# DE-260124.net
KiCad netlist of a schematic drawn in Altium Designer
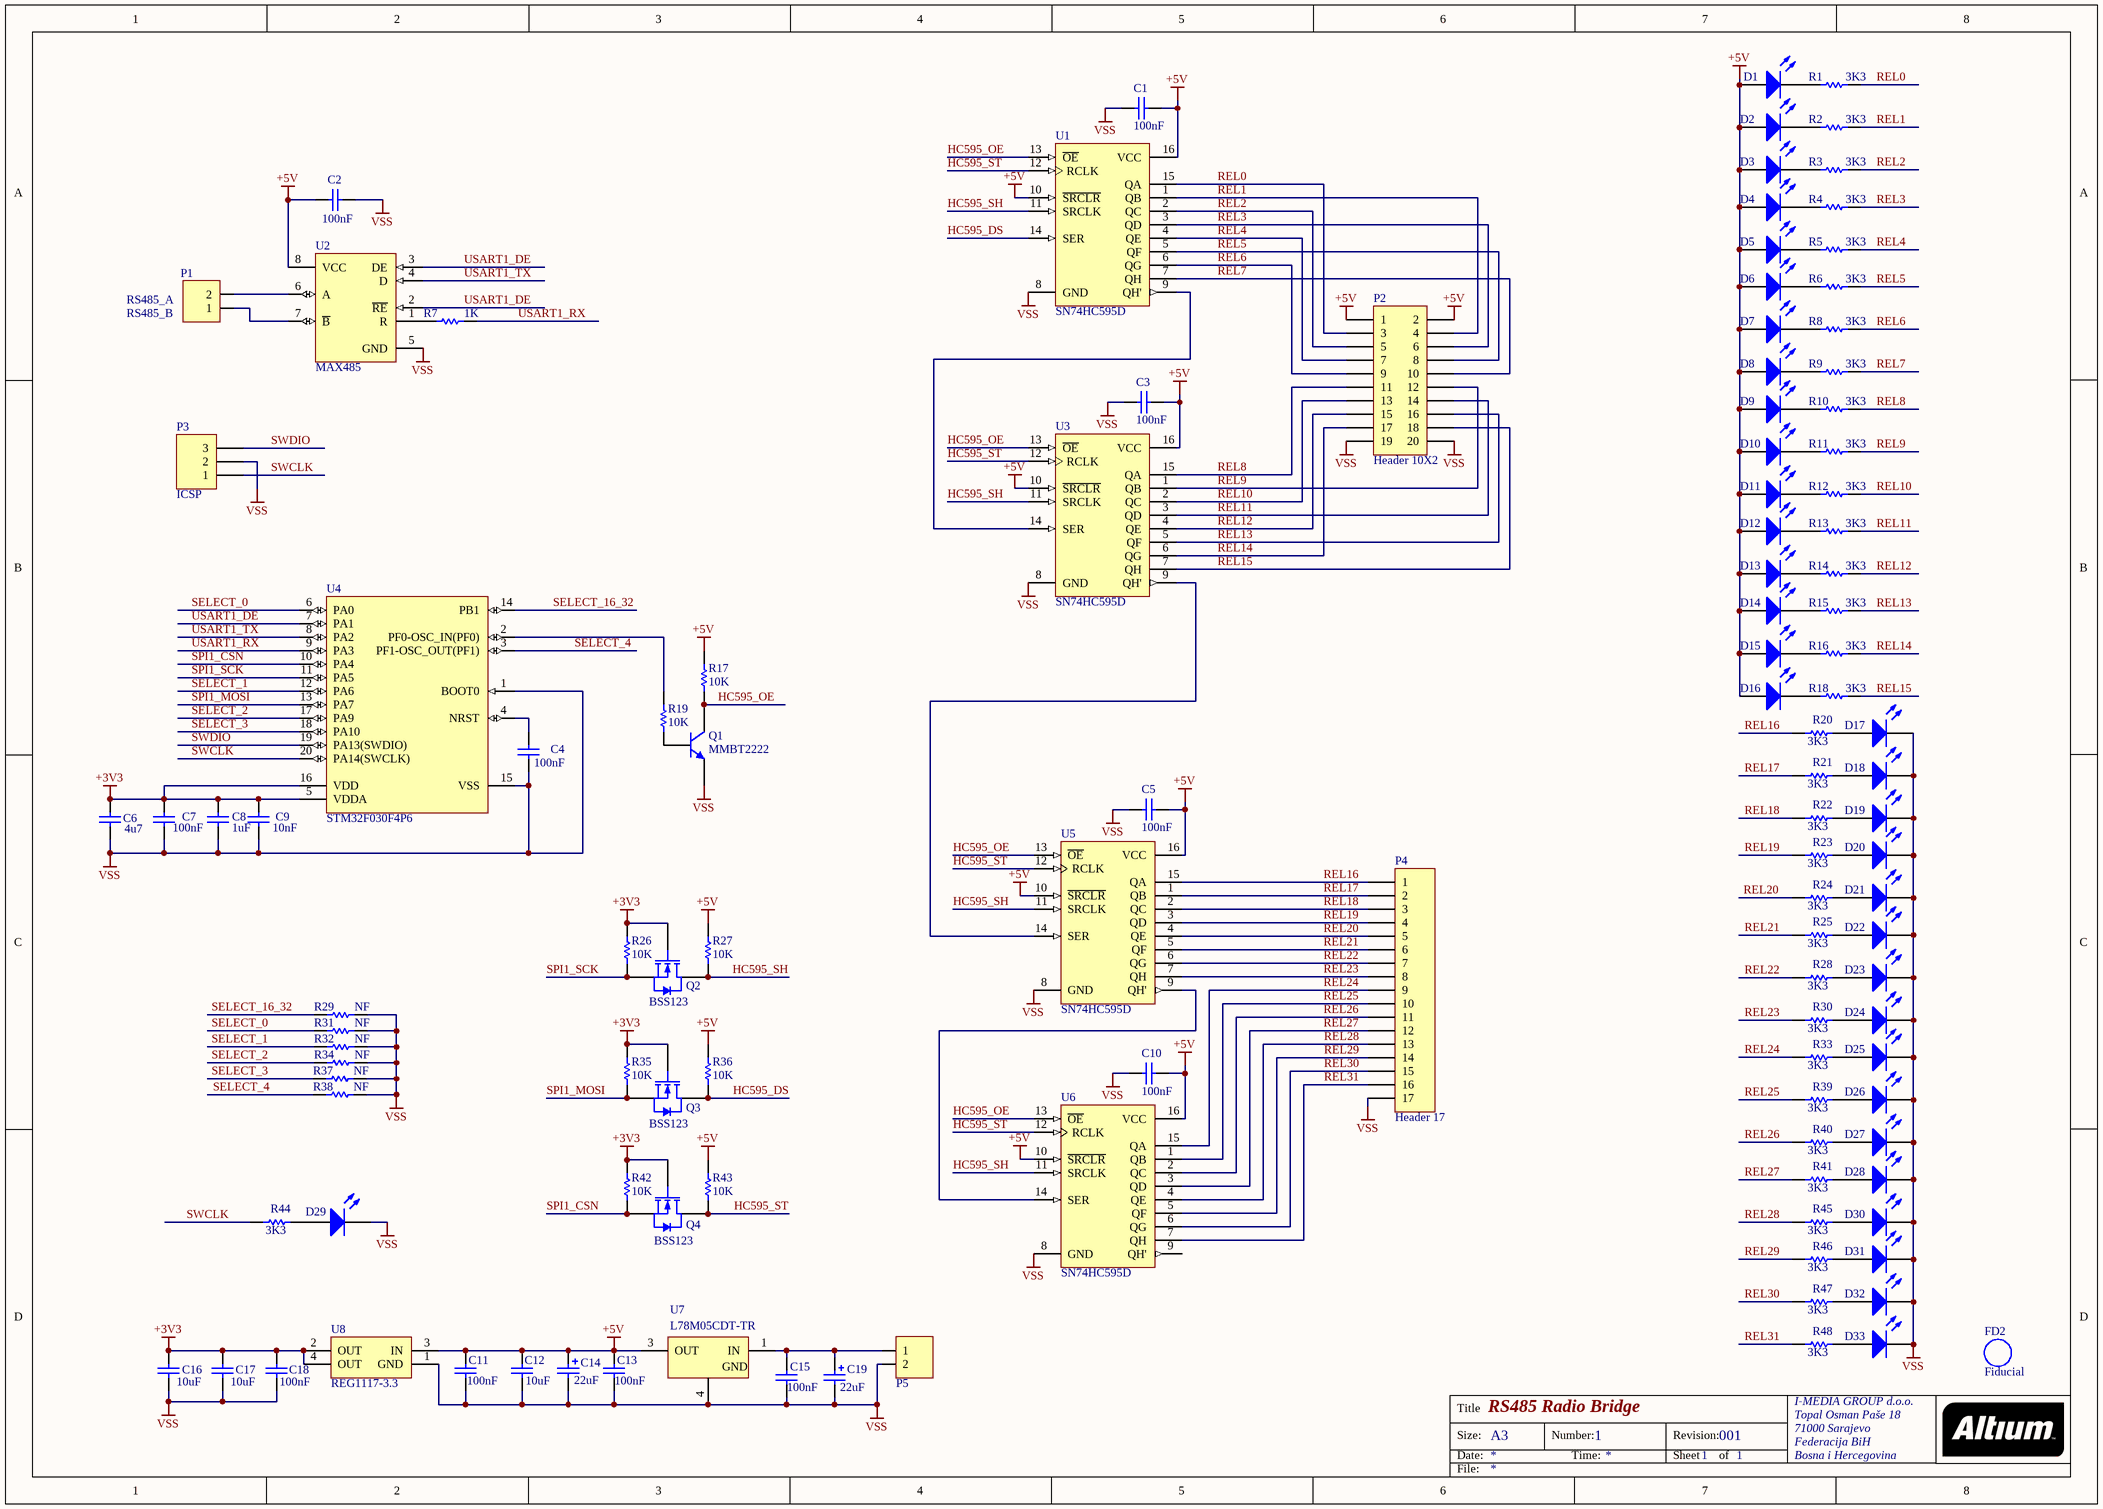
[diagram p0: DE-260124.SchDoc]

(export (version "E")
  (design (tool "Eeschema 10.0.6"))
  (components
    (comp (ref "C1")
      (value "100nF")
      (footprint "0603")
      (description "Ceramic Chip Capacitor - Standard")
      (libsource (lib "DE-251215") (part "C0603"))
    )
    (comp (ref "C2")
      (value "100nF")
      (footprint "0603")
      (description "Ceramic Chip Capacitor - Standard")
      (libsource (lib "KEMET Chip Capacitor") (part "C0603"))
    )
    (comp (ref "C3")
      (value "100nF")
      (footprint "0603")
      (description "Ceramic Chip Capacitor - Standard")
      (libsource (lib "DE-251215") (part "C0603"))
    )
    (comp (ref "C4")
      (value "100nF")
      (footprint "0603")
      (description "Ceramic Chip Capacitor - Standard")
      (libsource (lib "KEMET Chip Capacitor") (part "C0603"))
    )
    (comp (ref "C5")
      (value "100nF")
      (footprint "0603")
      (description "Ceramic Chip Capacitor - Standard")
      (libsource (lib "DE-251215") (part "C0603"))
    )
    (comp (ref "C6")
      (value "4u7")
      (footprint "0805")
      (description "Ceramic Chip Capacitor - Standard")
      (libsource (lib "KEMET Chip Capacitor") (part "C0805"))
    )
    (comp (ref "C7")
      (value "100nF")
      (footprint "0603")
      (description "Ceramic Chip Capacitor - Standard")
      (libsource (lib "KEMET Chip Capacitor") (part "C0603"))
    )
    (comp (ref "C8")
      (value "1uF")
      (footprint "0603")
      (description "Ceramic Chip Capacitor - Standard")
      (libsource (lib "KEMET Chip Capacitor") (part "C0603"))
    )
    (comp (ref "C9")
      (value "10nF")
      (footprint "0603")
      (description "Ceramic Chip Capacitor - Standard")
      (libsource (lib "KEMET Chip Capacitor") (part "C0603"))
    )
    (comp (ref "C10")
      (value "100nF")
      (footprint "0603")
      (description "Ceramic Chip Capacitor - Standard")
      (libsource (lib "DE-251215") (part "C0603"))
    )
    (comp (ref "C11")
      (value "100nF")
      (footprint "0603")
      (description "Ceramic Chip Capacitor - Standard")
      (libsource (lib "DE-251215") (part "C0603"))
    )
    (comp (ref "C12")
      (value "10uF")
      (footprint "0805")
      (description "Ceramic Chip Capacitor - Standard")
      (libsource (lib "DE-200216_03") (part "C0805"))
    )
    (comp (ref "C13")
      (value "100nF")
      (footprint "0603")
      (description "Ceramic Chip Capacitor - Standard")
      (libsource (lib "DE-251215") (part "C0603"))
    )
    (comp (ref "C14")
      (value "22uF")
      (footprint "CAPPR2-5X11")
      (description "Aluminum Electrolytic Capacitor, Radial Style with Long Leads: 47uF, 35V")
      (libsource (lib "DE-260124") (part "EKA00AA247F00"))
    )
    (comp (ref "C15")
      (value "100nF")
      (footprint "0603")
      (description "Ceramic Chip Capacitor - Standard")
      (libsource (lib "DE-251215") (part "C0603"))
    )
    (comp (ref "C16")
      (value "10uF")
      (footprint "0805")
      (description "Ceramic Chip Capacitor - Standard")
      (libsource (lib "DE-251215") (part "C0805"))
    )
    (comp (ref "C17")
      (value "10uF")
      (footprint "0805")
      (description "Ceramic Chip Capacitor - Standard")
      (libsource (lib "DE-251215") (part "C0805"))
    )
    (comp (ref "C18")
      (value "100nF")
      (footprint "0603")
      (description "Ceramic Chip Capacitor - Standard")
      (libsource (lib "DE-251215") (part "C0603"))
    )
    (comp (ref "C19")
      (value "22uF")
      (footprint "CAPPR2-5X11")
      (description "Aluminum Electrolytic Capacitor, Radial Style with Long Leads: 47uF, 35V")
      (libsource (lib "DE-260124") (part "EKA00AA247F00"))
    )
    (comp (ref "D1")
      (value "LED_RED")
      (footprint "1.6X0.8X0.8")
      (description "High Performance Chip LED, Red")
      (libsource (lib "DE-260124") (part "HSMZ-C190"))
    )
    (comp (ref "D2")
      (value "LED_RED")
      (footprint "1.6X0.8X0.8")
      (description "High Performance Chip LED, Red")
      (libsource (lib "DE-260124") (part "HSMZ-C190"))
    )
    (comp (ref "D3")
      (value "LED_RED")
      (footprint "1.6X0.8X0.8")
      (description "High Performance Chip LED, Red")
      (libsource (lib "DE-260124") (part "HSMZ-C190"))
    )
    (comp (ref "D4")
      (value "LED_RED")
      (footprint "1.6X0.8X0.8")
      (description "High Performance Chip LED, Red")
      (libsource (lib "DE-260124") (part "HSMZ-C190"))
    )
    (comp (ref "D5")
      (value "LED_RED")
      (footprint "1.6X0.8X0.8")
      (description "High Performance Chip LED, Red")
      (libsource (lib "DE-260124") (part "HSMZ-C190"))
    )
    (comp (ref "D6")
      (value "LED_RED")
      (footprint "1.6X0.8X0.8")
      (description "High Performance Chip LED, Red")
      (libsource (lib "DE-260124") (part "HSMZ-C190"))
    )
    (comp (ref "D7")
      (value "LED_RED")
      (footprint "1.6X0.8X0.8")
      (description "High Performance Chip LED, Red")
      (libsource (lib "DE-260124") (part "HSMZ-C190"))
    )
    (comp (ref "D8")
      (value "LED_RED")
      (footprint "1.6X0.8X0.8")
      (description "High Performance Chip LED, Red")
      (libsource (lib "DE-260124") (part "HSMZ-C190"))
    )
    (comp (ref "D9")
      (value "LED_RED")
      (footprint "1.6X0.8X0.8")
      (description "High Performance Chip LED, Red")
      (libsource (lib "DE-260124") (part "HSMZ-C190"))
    )
    (comp (ref "D10")
      (value "LED_RED")
      (footprint "1.6X0.8X0.8")
      (description "High Performance Chip LED, Red")
      (libsource (lib "DE-260124") (part "HSMZ-C190"))
    )
    (comp (ref "D11")
      (value "LED_RED")
      (footprint "1.6X0.8X0.8")
      (description "High Performance Chip LED, Red")
      (libsource (lib "DE-260124") (part "HSMZ-C190"))
    )
    (comp (ref "D12")
      (value "LED_RED")
      (footprint "1.6X0.8X0.8")
      (description "High Performance Chip LED, Red")
      (libsource (lib "DE-260124") (part "HSMZ-C190"))
    )
    (comp (ref "D13")
      (value "LED_RED")
      (footprint "1.6X0.8X0.8")
      (description "High Performance Chip LED, Red")
      (libsource (lib "DE-260124") (part "HSMZ-C190"))
    )
    (comp (ref "D14")
      (value "LED_RED")
      (footprint "1.6X0.8X0.8")
      (description "High Performance Chip LED, Red")
      (libsource (lib "DE-260124") (part "HSMZ-C190"))
    )
    (comp (ref "D15")
      (value "LED_RED")
      (footprint "1.6X0.8X0.8")
      (description "High Performance Chip LED, Red")
      (libsource (lib "DE-260124") (part "HSMZ-C190"))
    )
    (comp (ref "D16")
      (value "LED_RED")
      (footprint "1.6X0.8X0.8")
      (description "High Performance Chip LED, Red")
      (libsource (lib "DE-260124") (part "HSMZ-C190"))
    )
    (comp (ref "D17")
      (value "LED_RED")
      (footprint "1.6X0.8X0.8")
      (description "High Performance Chip LED, Red")
      (libsource (lib "DE-260124") (part "HSMZ-C190"))
    )
    (comp (ref "D18")
      (value "LED_RED")
      (footprint "1.6X0.8X0.8")
      (description "High Performance Chip LED, Red")
      (libsource (lib "DE-260124") (part "HSMZ-C190"))
    )
    (comp (ref "D19")
      (value "LED_RED")
      (footprint "1.6X0.8X0.8")
      (description "High Performance Chip LED, Red")
      (libsource (lib "DE-260124") (part "HSMZ-C190"))
    )
    (comp (ref "D20")
      (value "LED_RED")
      (footprint "1.6X0.8X0.8")
      (description "High Performance Chip LED, Red")
      (libsource (lib "DE-260124") (part "HSMZ-C190"))
    )
    (comp (ref "D21")
      (value "LED_RED")
      (footprint "1.6X0.8X0.8")
      (description "High Performance Chip LED, Red")
      (libsource (lib "DE-260124") (part "HSMZ-C190"))
    )
    (comp (ref "D22")
      (value "LED_RED")
      (footprint "1.6X0.8X0.8")
      (description "High Performance Chip LED, Red")
      (libsource (lib "DE-260124") (part "HSMZ-C190"))
    )
    (comp (ref "D23")
      (value "LED_RED")
      (footprint "1.6X0.8X0.8")
      (description "High Performance Chip LED, Red")
      (libsource (lib "DE-260124") (part "HSMZ-C190"))
    )
    (comp (ref "D24")
      (value "LED_RED")
      (footprint "1.6X0.8X0.8")
      (description "High Performance Chip LED, Red")
      (libsource (lib "DE-260124") (part "HSMZ-C190"))
    )
    (comp (ref "D25")
      (value "LED_RED")
      (footprint "1.6X0.8X0.8")
      (description "High Performance Chip LED, Red")
      (libsource (lib "DE-260124") (part "HSMZ-C190"))
    )
    (comp (ref "D26")
      (value "LED_RED")
      (footprint "1.6X0.8X0.8")
      (description "High Performance Chip LED, Red")
      (libsource (lib "DE-260124") (part "HSMZ-C190"))
    )
    (comp (ref "D27")
      (value "LED_RED")
      (footprint "1.6X0.8X0.8")
      (description "High Performance Chip LED, Red")
      (libsource (lib "DE-260124") (part "HSMZ-C190"))
    )
    (comp (ref "D28")
      (value "LED_RED")
      (footprint "1.6X0.8X0.8")
      (description "High Performance Chip LED, Red")
      (libsource (lib "DE-260124") (part "HSMZ-C190"))
    )
    (comp (ref "D29")
      (value "LED_RED")
      (footprint "1.6X0.8X0.8")
      (description "High Performance Chip LED, Red")
      (libsource (lib "DE-260124") (part "HSMZ-C190"))
    )
    (comp (ref "D30")
      (value "LED_RED")
      (footprint "1.6X0.8X0.8")
      (description "High Performance Chip LED, Red")
      (libsource (lib "DE-260124") (part "HSMZ-C190"))
    )
    (comp (ref "D31")
      (value "LED_RED")
      (footprint "1.6X0.8X0.8")
      (description "High Performance Chip LED, Red")
      (libsource (lib "DE-260124") (part "HSMZ-C190"))
    )
    (comp (ref "D32")
      (value "LED_RED")
      (footprint "1.6X0.8X0.8")
      (description "High Performance Chip LED, Red")
      (libsource (lib "DE-260124") (part "HSMZ-C190"))
    )
    (comp (ref "D33")
      (value "LED_RED")
      (footprint "1.6X0.8X0.8")
      (description "High Performance Chip LED, Red")
      (libsource (lib "DE-260124") (part "HSMZ-C190"))
    )
    (comp (ref "FD2")
      (value "Fiducial")
      (footprint "Fiducial")
      (description "Fiduchial mark")
      (libsource (lib "DE-260124") (part "Fiduchial"))
    )
    (comp (ref "P1")
      (value "TERMINAL BLOK 2")
      (footprint "TERMINAL BLOK 2")
      (description "2 pinski terminal blok")
      (libsource (lib "DE-280817") (part "TERMINAL BLOK 2"))
    )
    (comp (ref "P2")
      (value "Header 10X2")
      (footprint "HDR2X10")
      (description "Header, 10-Pin, Dual row")
      (libsource (lib "Miscellaneous Connectors") (part "Header 10X2"))
    )
    (comp (ref "P3")
      (value "ICSP")
      (footprint "HDR1X3")
      (description "Header, 3-Pin")
      (libsource (lib "Miscellaneous Connectors") (part "Header 3"))
    )
    (comp (ref "P4")
      (value "Header 17")
      (footprint "HDR1X17")
      (description "Header, 17-Pin")
      (libsource (lib "Miscellaneous Connectors") (part "Header 17"))
    )
    (comp (ref "P5")
      (value "TERMINAL BLOK 2")
      (footprint "TERMINAL BLOK 2")
      (description "2 pinski terminal blok")
      (libsource (lib "DE-260124") (part "TERMINAL BLOK 2"))
    )
    (comp (ref "Q1")
      (value "MMBT2222")
      (footprint "SOT23_N")
      (description "NPN General-purpose Transistor")
      (libsource (lib "DE-260124") (part "BC817"))
    )
    (comp (ref "Q2")
      (value "BSS123")
      (footprint "SOT23_N")
      (description "N-channel Enhancement Mode Vertical D-MOSFET")
      (libsource (lib "DE-260124") (part "BSS123"))
    )
    (comp (ref "Q3")
      (value "BSS123")
      (footprint "SOT23_N")
      (description "N-channel Enhancement Mode Vertical D-MOSFET")
      (libsource (lib "DE-260124") (part "BSS123"))
    )
    (comp (ref "Q4")
      (value "BSS123")
      (footprint "SOT23_N")
      (description "N-channel Enhancement Mode Vertical D-MOSFET")
      (libsource (lib "DE-260124") (part "BSS123"))
    )
    (comp (ref "R1")
      (value "3K3")
      (footprint "ERA-0603")
      (libsource (lib "Panasonic Resistor") (part "ERA3Y"))
    )
    (comp (ref "R2")
      (value "3K3")
      (footprint "ERA-0603")
      (libsource (lib "Panasonic Resistor") (part "ERA3Y"))
    )
    (comp (ref "R3")
      (value "3K3")
      (footprint "ERA-0603")
      (libsource (lib "Panasonic Resistor") (part "ERA3Y"))
    )
    (comp (ref "R4")
      (value "3K3")
      (footprint "ERA-0603")
      (libsource (lib "Panasonic Resistor") (part "ERA3Y"))
    )
    (comp (ref "R5")
      (value "3K3")
      (footprint "ERA-0603")
      (libsource (lib "Panasonic Resistor") (part "ERA3Y"))
    )
    (comp (ref "R6")
      (value "3K3")
      (footprint "ERA-0603")
      (libsource (lib "Panasonic Resistor") (part "ERA3Y"))
    )
    (comp (ref "R7") (value "1K") (footprint "ERA-0603") (libsource (lib "DE-280817") (part "ERA6Y")))
    (comp (ref "R8")
      (value "3K3")
      (footprint "ERA-0603")
      (libsource (lib "Panasonic Resistor") (part "ERA3Y"))
    )
    (comp (ref "R9")
      (value "3K3")
      (footprint "ERA-0603")
      (libsource (lib "Panasonic Resistor") (part "ERA3Y"))
    )
    (comp (ref "R10")
      (value "3K3")
      (footprint "ERA-0603")
      (libsource (lib "Panasonic Resistor") (part "ERA3Y"))
    )
    (comp (ref "R11")
      (value "3K3")
      (footprint "ERA-0603")
      (libsource (lib "Panasonic Resistor") (part "ERA3Y"))
    )
    (comp (ref "R12")
      (value "3K3")
      (footprint "ERA-0603")
      (libsource (lib "Panasonic Resistor") (part "ERA3Y"))
    )
    (comp (ref "R13")
      (value "3K3")
      (footprint "ERA-0603")
      (libsource (lib "Panasonic Resistor") (part "ERA3Y"))
    )
    (comp (ref "R14")
      (value "3K3")
      (footprint "ERA-0603")
      (libsource (lib "Panasonic Resistor") (part "ERA3Y"))
    )
    (comp (ref "R15")
      (value "3K3")
      (footprint "ERA-0603")
      (libsource (lib "Panasonic Resistor") (part "ERA3Y"))
    )
    (comp (ref "R16")
      (value "3K3")
      (footprint "ERA-0603")
      (libsource (lib "Panasonic Resistor") (part "ERA3Y"))
    )
    (comp (ref "R17") (value "10K") (footprint "ERA-0603") (libsource (lib "DE-280817") (part "ERA6Y")))
    (comp (ref "R18")
      (value "3K3")
      (footprint "ERA-0603")
      (libsource (lib "Panasonic Resistor") (part "ERA3Y"))
    )
    (comp (ref "R19") (value "10K") (footprint "ERA-0603") (libsource (lib "DE-280817") (part "ERA6Y")))
    (comp (ref "R20")
      (value "3K3")
      (footprint "ERA-0603")
      (libsource (lib "Panasonic Resistor") (part "ERA3Y"))
    )
    (comp (ref "R21")
      (value "3K3")
      (footprint "ERA-0603")
      (libsource (lib "Panasonic Resistor") (part "ERA3Y"))
    )
    (comp (ref "R22")
      (value "3K3")
      (footprint "ERA-0603")
      (libsource (lib "Panasonic Resistor") (part "ERA3Y"))
    )
    (comp (ref "R23")
      (value "3K3")
      (footprint "ERA-0603")
      (libsource (lib "Panasonic Resistor") (part "ERA3Y"))
    )
    (comp (ref "R24")
      (value "3K3")
      (footprint "ERA-0603")
      (libsource (lib "Panasonic Resistor") (part "ERA3Y"))
    )
    (comp (ref "R25")
      (value "3K3")
      (footprint "ERA-0603")
      (libsource (lib "Panasonic Resistor") (part "ERA3Y"))
    )
    (comp (ref "R26") (value "10K") (footprint "ERA-0603") (libsource (lib "DE-280817") (part "ERA6Y")))
    (comp (ref "R27") (value "10K") (footprint "ERA-0603") (libsource (lib "DE-280817") (part "ERA6Y")))
    (comp (ref "R28")
      (value "3K3")
      (footprint "ERA-0603")
      (libsource (lib "Panasonic Resistor") (part "ERA3Y"))
    )
    (comp (ref "R29") (value "NF") (footprint "ERA-0603") (libsource (lib "DE-280817") (part "ERA6Y")))
    (comp (ref "R30")
      (value "3K3")
      (footprint "ERA-0603")
      (libsource (lib "Panasonic Resistor") (part "ERA3Y"))
    )
    (comp (ref "R31") (value "NF") (footprint "ERA-0603") (libsource (lib "DE-280817") (part "ERA6Y")))
    (comp (ref "R32") (value "NF") (footprint "ERA-0603") (libsource (lib "DE-280817") (part "ERA6Y")))
    (comp (ref "R33")
      (value "3K3")
      (footprint "ERA-0603")
      (libsource (lib "Panasonic Resistor") (part "ERA3Y"))
    )
    (comp (ref "R34") (value "NF") (footprint "ERA-0603") (libsource (lib "DE-280817") (part "ERA6Y")))
    (comp (ref "R35") (value "10K") (footprint "ERA-0603") (libsource (lib "DE-280817") (part "ERA6Y")))
    (comp (ref "R36") (value "10K") (footprint "ERA-0603") (libsource (lib "DE-280817") (part "ERA6Y")))
    (comp (ref "R37") (value "NF") (footprint "ERA-0603") (libsource (lib "DE-280817") (part "ERA6Y")))
    (comp (ref "R38") (value "NF") (footprint "ERA-0603") (libsource (lib "DE-280817") (part "ERA6Y")))
    (comp (ref "R39")
      (value "3K3")
      (footprint "ERA-0603")
      (libsource (lib "Panasonic Resistor") (part "ERA3Y"))
    )
    (comp (ref "R40")
      (value "3K3")
      (footprint "ERA-0603")
      (libsource (lib "Panasonic Resistor") (part "ERA3Y"))
    )
    (comp (ref "R41")
      (value "3K3")
      (footprint "ERA-0603")
      (libsource (lib "Panasonic Resistor") (part "ERA3Y"))
    )
    (comp (ref "R42") (value "10K") (footprint "ERA-0603") (libsource (lib "DE-280817") (part "ERA6Y")))
    (comp (ref "R43") (value "10K") (footprint "ERA-0603") (libsource (lib "DE-280817") (part "ERA6Y")))
    (comp (ref "R44")
      (value "3K3")
      (footprint "ERA-0603")
      (libsource (lib "Panasonic Resistor") (part "ERA3Y"))
    )
    (comp (ref "R45")
      (value "3K3")
      (footprint "ERA-0603")
      (libsource (lib "Panasonic Resistor") (part "ERA3Y"))
    )
    (comp (ref "R46")
      (value "3K3")
      (footprint "ERA-0603")
      (libsource (lib "Panasonic Resistor") (part "ERA3Y"))
    )
    (comp (ref "R47")
      (value "3K3")
      (footprint "ERA-0603")
      (libsource (lib "Panasonic Resistor") (part "ERA3Y"))
    )
    (comp (ref "R48")
      (value "3K3")
      (footprint "ERA-0603")
      (libsource (lib "Panasonic Resistor") (part "ERA3Y"))
    )
    (comp (ref "U1")
      (value "SN74HC595D")
      (footprint "D016_N")
      (description "8-Bit Shift Register with 3-State Output Registers")
      (libsource (lib "DE-260124") (part "SN74HC595D"))
    )
    (comp (ref "U2")
      (value "MAX485")
      (footprint "D008_L")
      (description "Differential Bus Transceiver")
      (libsource (lib "DE-280817") (part "SN75176BD"))
    )
    (comp (ref "U3")
      (value "SN74HC595D")
      (footprint "D016_N")
      (description "8-Bit Shift Register with 3-State Output Registers")
      (libsource (lib "DE-260124") (part "SN74HC595D"))
    )
    (comp (ref "U4")
      (value "STM32F030F4P6")
      (footprint "STM-TSSOP20_N")
      (libsource (lib "STMicroelectronics STM32 F0") (part "STM32F030F4P6"))
    )
    (comp (ref "U5")
      (value "SN74HC595D")
      (footprint "D016_N")
      (description "8-Bit Shift Register with 3-State Output Registers")
      (libsource (lib "DE-260124") (part "SN74HC595D"))
    )
    (comp (ref "U6")
      (value "SN74HC595D")
      (footprint "D016_N")
      (description "8-Bit Shift Register with 3-State Output Registers")
      (libsource (lib "DE-260124") (part "SN74HC595D"))
    )
    (comp (ref "U7")
      (value "L78M05CDT-TR")
      (footprint "TO-252_N")
      (description "Positive Voltage Regulator, 5V, 3-Pin DPAK, Tape and Reel")
      (libsource (lib "DE-260124") (part "L78M05CDT-TR"))
    )
    (comp (ref "U8")
      (value "REG1117-3.3")
      (footprint "ZZ311")
      (description "800mA and 1A Low Dropout Positive Regulator 2.85V, 3.3V, 5V, and Adjustable")
      (libsource (lib "DE-251215") (part "REG1117-3.3"))
    )
  )
  (nets
    (net (code "1") (name "+3V3") (class "Default")
      (node (ref "C16") (pin "2") (pinfunction "2_2") (pintype "passive"))
      (node (ref "C17") (pin "2") (pinfunction "2_2") (pintype "passive"))
      (node (ref "C18") (pin "2") (pinfunction "2_2") (pintype "passive"))
      (node (ref "C6") (pin "1") (pinfunction "1_1") (pintype "passive"))
      (node (ref "C7") (pin "1") (pinfunction "1_1") (pintype "passive"))
      (node (ref "C8") (pin "1") (pinfunction "1_1") (pintype "passive"))
      (node (ref "C9") (pin "1") (pinfunction "1_1") (pintype "passive"))
      (node (ref "Q2") (pin "1") (pinfunction "G_1") (pintype "passive"))
      (node (ref "Q3") (pin "1") (pinfunction "G_1") (pintype "passive"))
      (node (ref "Q4") (pin "1") (pinfunction "G_1") (pintype "passive"))
      (node (ref "R26") (pin "1") (pinfunction "1_1") (pintype "passive"))
      (node (ref "R35") (pin "1") (pinfunction "1_1") (pintype "passive"))
      (node (ref "R42") (pin "1") (pinfunction "1_1") (pintype "passive"))
      (node (ref "U4") (pin "16") (pinfunction "VDD_16") (pintype "power_in"))
      (node (ref "U4") (pin "5") (pinfunction "VDDA_5") (pintype "power_in"))
      (node (ref "U8") (pin "2") (pinfunction "OUT_2") (pintype "power_in"))
      (node (ref "U8") (pin "4") (pinfunction "OUT_4") (pintype "power_in"))
    )
    (net (code "2") (name "+5V") (class "Default")
      (node (ref "C1") (pin "1") (pinfunction "1_1") (pintype "passive"))
      (node (ref "C10") (pin "1") (pinfunction "1_1") (pintype "passive"))
      (node (ref "C11") (pin "2") (pinfunction "2_2") (pintype "passive"))
      (node (ref "C12") (pin "2") (pinfunction "2_2") (pintype "passive"))
      (node (ref "C13") (pin "2") (pinfunction "2_2") (pintype "passive"))
      (node (ref "C14") (pin "1") (pinfunction "1_1") (pintype "passive"))
      (node (ref "C2") (pin "1") (pinfunction "1_1") (pintype "passive"))
      (node (ref "C3") (pin "1") (pinfunction "1_1") (pintype "passive"))
      (node (ref "C5") (pin "1") (pinfunction "1_1") (pintype "passive"))
      (node (ref "D1") (pin "1") (pinfunction "A_1") (pintype "passive"))
      (node (ref "D10") (pin "1") (pinfunction "A_1") (pintype "passive"))
      (node (ref "D11") (pin "1") (pinfunction "A_1") (pintype "passive"))
      (node (ref "D12") (pin "1") (pinfunction "A_1") (pintype "passive"))
      (node (ref "D13") (pin "1") (pinfunction "A_1") (pintype "passive"))
      (node (ref "D14") (pin "1") (pinfunction "A_1") (pintype "passive"))
      (node (ref "D15") (pin "1") (pinfunction "A_1") (pintype "passive"))
      (node (ref "D16") (pin "1") (pinfunction "A_1") (pintype "passive"))
      (node (ref "D2") (pin "1") (pinfunction "A_1") (pintype "passive"))
      (node (ref "D3") (pin "1") (pinfunction "A_1") (pintype "passive"))
      (node (ref "D4") (pin "1") (pinfunction "A_1") (pintype "passive"))
      (node (ref "D5") (pin "1") (pinfunction "A_1") (pintype "passive"))
      (node (ref "D6") (pin "1") (pinfunction "A_1") (pintype "passive"))
      (node (ref "D7") (pin "1") (pinfunction "A_1") (pintype "passive"))
      (node (ref "D8") (pin "1") (pinfunction "A_1") (pintype "passive"))
      (node (ref "D9") (pin "1") (pinfunction "A_1") (pintype "passive"))
      (node (ref "P2") (pin "1") (pinfunction "1_1") (pintype "passive"))
      (node (ref "P2") (pin "2") (pinfunction "2_2") (pintype "passive"))
      (node (ref "R17") (pin "1") (pinfunction "1_1") (pintype "passive"))
      (node (ref "R27") (pin "1") (pinfunction "1_1") (pintype "passive"))
      (node (ref "R36") (pin "1") (pinfunction "1_1") (pintype "passive"))
      (node (ref "R43") (pin "1") (pinfunction "1_1") (pintype "passive"))
      (node (ref "U1") (pin "10") (pinfunction "~{SRCLR}_10") (pintype "input"))
      (node (ref "U1") (pin "16") (pinfunction "VCC_16") (pintype "power_in"))
      (node (ref "U2") (pin "8") (pinfunction "VCC_8") (pintype "power_in"))
      (node (ref "U3") (pin "10") (pinfunction "~{SRCLR}_10") (pintype "input"))
      (node (ref "U3") (pin "16") (pinfunction "VCC_16") (pintype "power_in"))
      (node (ref "U5") (pin "10") (pinfunction "~{SRCLR}_10") (pintype "input"))
      (node (ref "U5") (pin "16") (pinfunction "VCC_16") (pintype "power_in"))
      (node (ref "U6") (pin "10") (pinfunction "~{SRCLR}_10") (pintype "input"))
      (node (ref "U6") (pin "16") (pinfunction "VCC_16") (pintype "power_in"))
      (node (ref "U7") (pin "3") (pinfunction "OUT_3") (pintype "power_in"))
      (node (ref "U8") (pin "3") (pinfunction "IN_3") (pintype "power_in"))
    )
    (net (code "3") (name "/HC595_DS") (class "Default")
      (node (ref "Q3") (pin "3") (pinfunction "D_3") (pintype "passive"))
      (node (ref "R36") (pin "2") (pinfunction "2_2") (pintype "passive"))
      (node (ref "U1") (pin "14") (pinfunction "SER_14") (pintype "input"))
    )
    (net (code "4") (name "/HC595_OE") (class "Default")
      (node (ref "Q1") (pin "3") (pinfunction "C_3") (pintype "passive"))
      (node (ref "R17") (pin "2") (pinfunction "2_2") (pintype "passive"))
      (node (ref "U1") (pin "13") (pinfunction "~{OE}_13") (pintype "input"))
      (node (ref "U3") (pin "13") (pinfunction "~{OE}_13") (pintype "input"))
      (node (ref "U5") (pin "13") (pinfunction "~{OE}_13") (pintype "input"))
      (node (ref "U6") (pin "13") (pinfunction "~{OE}_13") (pintype "input"))
    )
    (net (code "5") (name "/HC595_SH") (class "Default")
      (node (ref "Q2") (pin "3") (pinfunction "D_3") (pintype "passive"))
      (node (ref "R27") (pin "2") (pinfunction "2_2") (pintype "passive"))
      (node (ref "U1") (pin "11") (pinfunction "SRCLK_11") (pintype "input"))
      (node (ref "U3") (pin "11") (pinfunction "SRCLK_11") (pintype "input"))
      (node (ref "U5") (pin "11") (pinfunction "SRCLK_11") (pintype "input"))
      (node (ref "U6") (pin "11") (pinfunction "SRCLK_11") (pintype "input"))
    )
    (net (code "6") (name "/HC595_ST") (class "Default")
      (node (ref "Q4") (pin "3") (pinfunction "D_3") (pintype "passive"))
      (node (ref "R43") (pin "2") (pinfunction "2_2") (pintype "passive"))
      (node (ref "U1") (pin "12") (pinfunction "RCLK_12") (pintype "input"))
      (node (ref "U3") (pin "12") (pinfunction "RCLK_12") (pintype "input"))
      (node (ref "U5") (pin "12") (pinfunction "RCLK_12") (pintype "input"))
      (node (ref "U6") (pin "12") (pinfunction "RCLK_12") (pintype "input"))
    )
    (net (code "7") (name "/REL0") (class "Default")
      (node (ref "P2") (pin "3") (pinfunction "3_3") (pintype "passive"))
      (node (ref "R1") (pin "2") (pinfunction "2_2") (pintype "passive"))
      (node (ref "U1") (pin "15") (pinfunction "QA_15") (pintype "tri_state"))
    )
    (net (code "8") (name "/REL1") (class "Default")
      (node (ref "P2") (pin "4") (pinfunction "4_4") (pintype "passive"))
      (node (ref "R2") (pin "2") (pinfunction "2_2") (pintype "passive"))
      (node (ref "U1") (pin "1") (pinfunction "QB_1") (pintype "tri_state"))
    )
    (net (code "9") (name "/REL2") (class "Default")
      (node (ref "P2") (pin "5") (pinfunction "5_5") (pintype "passive"))
      (node (ref "R3") (pin "2") (pinfunction "2_2") (pintype "passive"))
      (node (ref "U1") (pin "2") (pinfunction "QC_2") (pintype "tri_state"))
    )
    (net (code "10") (name "/REL3") (class "Default")
      (node (ref "P2") (pin "6") (pinfunction "6_6") (pintype "passive"))
      (node (ref "R4") (pin "2") (pinfunction "2_2") (pintype "passive"))
      (node (ref "U1") (pin "3") (pinfunction "QD_3") (pintype "tri_state"))
    )
    (net (code "11") (name "/REL4") (class "Default")
      (node (ref "P2") (pin "7") (pinfunction "7_7") (pintype "passive"))
      (node (ref "R5") (pin "2") (pinfunction "2_2") (pintype "passive"))
      (node (ref "U1") (pin "4") (pinfunction "QE_4") (pintype "tri_state"))
    )
    (net (code "12") (name "/REL5") (class "Default")
      (node (ref "P2") (pin "8") (pinfunction "8_8") (pintype "passive"))
      (node (ref "R6") (pin "2") (pinfunction "2_2") (pintype "passive"))
      (node (ref "U1") (pin "5") (pinfunction "QF_5") (pintype "tri_state"))
    )
    (net (code "13") (name "/REL6") (class "Default")
      (node (ref "P2") (pin "9") (pinfunction "9_9") (pintype "passive"))
      (node (ref "R8") (pin "2") (pinfunction "2_2") (pintype "passive"))
      (node (ref "U1") (pin "6") (pinfunction "QG_6") (pintype "tri_state"))
    )
    (net (code "14") (name "/REL7") (class "Default")
      (node (ref "P2") (pin "10") (pinfunction "10_10") (pintype "passive"))
      (node (ref "R9") (pin "2") (pinfunction "2_2") (pintype "passive"))
      (node (ref "U1") (pin "7") (pinfunction "QH_7") (pintype "tri_state"))
    )
    (net (code "15") (name "/REL8") (class "Default")
      (node (ref "P2") (pin "11") (pinfunction "11_11") (pintype "passive"))
      (node (ref "R10") (pin "2") (pinfunction "2_2") (pintype "passive"))
      (node (ref "U3") (pin "15") (pinfunction "QA_15") (pintype "tri_state"))
    )
    (net (code "16") (name "/REL9") (class "Default")
      (node (ref "P2") (pin "12") (pinfunction "12_12") (pintype "passive"))
      (node (ref "R11") (pin "2") (pinfunction "2_2") (pintype "passive"))
      (node (ref "U3") (pin "1") (pinfunction "QB_1") (pintype "tri_state"))
    )
    (net (code "17") (name "/REL10") (class "Default")
      (node (ref "P2") (pin "13") (pinfunction "13_13") (pintype "passive"))
      (node (ref "R12") (pin "2") (pinfunction "2_2") (pintype "passive"))
      (node (ref "U3") (pin "2") (pinfunction "QC_2") (pintype "tri_state"))
    )
    (net (code "18") (name "/REL11") (class "Default")
      (node (ref "P2") (pin "14") (pinfunction "14_14") (pintype "passive"))
      (node (ref "R13") (pin "2") (pinfunction "2_2") (pintype "passive"))
      (node (ref "U3") (pin "3") (pinfunction "QD_3") (pintype "tri_state"))
    )
    (net (code "19") (name "/REL12") (class "Default")
      (node (ref "P2") (pin "15") (pinfunction "15_15") (pintype "passive"))
      (node (ref "R14") (pin "2") (pinfunction "2_2") (pintype "passive"))
      (node (ref "U3") (pin "4") (pinfunction "QE_4") (pintype "tri_state"))
    )
    (net (code "20") (name "/REL13") (class "Default")
      (node (ref "P2") (pin "16") (pinfunction "16_16") (pintype "passive"))
      (node (ref "R15") (pin "2") (pinfunction "2_2") (pintype "passive"))
      (node (ref "U3") (pin "5") (pinfunction "QF_5") (pintype "tri_state"))
    )
    (net (code "21") (name "/REL14") (class "Default")
      (node (ref "P2") (pin "17") (pinfunction "17_17") (pintype "passive"))
      (node (ref "R16") (pin "2") (pinfunction "2_2") (pintype "passive"))
      (node (ref "U3") (pin "6") (pinfunction "QG_6") (pintype "tri_state"))
    )
    (net (code "22") (name "/REL15") (class "Default")
      (node (ref "P2") (pin "18") (pinfunction "18_18") (pintype "passive"))
      (node (ref "R18") (pin "2") (pinfunction "2_2") (pintype "passive"))
      (node (ref "U3") (pin "7") (pinfunction "QH_7") (pintype "tri_state"))
    )
    (net (code "23") (name "/REL16") (class "Default")
      (node (ref "P4") (pin "1") (pinfunction "1_1") (pintype "passive"))
      (node (ref "R20") (pin "1") (pinfunction "1_1") (pintype "passive"))
      (node (ref "U5") (pin "15") (pinfunction "QA_15") (pintype "tri_state"))
    )
    (net (code "24") (name "/REL17") (class "Default")
      (node (ref "P4") (pin "2") (pinfunction "2_2") (pintype "passive"))
      (node (ref "R21") (pin "1") (pinfunction "1_1") (pintype "passive"))
      (node (ref "U5") (pin "1") (pinfunction "QB_1") (pintype "tri_state"))
    )
    (net (code "25") (name "/REL18") (class "Default")
      (node (ref "P4") (pin "3") (pinfunction "3_3") (pintype "passive"))
      (node (ref "R22") (pin "1") (pinfunction "1_1") (pintype "passive"))
      (node (ref "U5") (pin "2") (pinfunction "QC_2") (pintype "tri_state"))
    )
    (net (code "26") (name "/REL19") (class "Default")
      (node (ref "P4") (pin "4") (pinfunction "4_4") (pintype "passive"))
      (node (ref "R23") (pin "1") (pinfunction "1_1") (pintype "passive"))
      (node (ref "U5") (pin "3") (pinfunction "QD_3") (pintype "tri_state"))
    )
    (net (code "27") (name "/REL20") (class "Default")
      (node (ref "P4") (pin "5") (pinfunction "5_5") (pintype "passive"))
      (node (ref "R24") (pin "1") (pinfunction "1_1") (pintype "passive"))
      (node (ref "U5") (pin "4") (pinfunction "QE_4") (pintype "tri_state"))
    )
    (net (code "28") (name "/REL21") (class "Default")
      (node (ref "P4") (pin "6") (pinfunction "6_6") (pintype "passive"))
      (node (ref "R25") (pin "1") (pinfunction "1_1") (pintype "passive"))
      (node (ref "U5") (pin "5") (pinfunction "QF_5") (pintype "tri_state"))
    )
    (net (code "29") (name "/REL22") (class "Default")
      (node (ref "P4") (pin "7") (pinfunction "7_7") (pintype "passive"))
      (node (ref "R28") (pin "1") (pinfunction "1_1") (pintype "passive"))
      (node (ref "U5") (pin "6") (pinfunction "QG_6") (pintype "tri_state"))
    )
    (net (code "30") (name "/REL23") (class "Default")
      (node (ref "P4") (pin "8") (pinfunction "8_8") (pintype "passive"))
      (node (ref "R30") (pin "1") (pinfunction "1_1") (pintype "passive"))
      (node (ref "U5") (pin "7") (pinfunction "QH_7") (pintype "tri_state"))
    )
    (net (code "31") (name "/REL24") (class "Default")
      (node (ref "P4") (pin "9") (pinfunction "9_9") (pintype "passive"))
      (node (ref "R33") (pin "1") (pinfunction "1_1") (pintype "passive"))
      (node (ref "U6") (pin "15") (pinfunction "QA_15") (pintype "tri_state"))
    )
    (net (code "32") (name "/REL25") (class "Default")
      (node (ref "P4") (pin "10") (pinfunction "10_10") (pintype "passive"))
      (node (ref "R39") (pin "1") (pinfunction "1_1") (pintype "passive"))
      (node (ref "U6") (pin "1") (pinfunction "QB_1") (pintype "tri_state"))
    )
    (net (code "33") (name "/REL26") (class "Default")
      (node (ref "P4") (pin "11") (pinfunction "11_11") (pintype "passive"))
      (node (ref "R40") (pin "1") (pinfunction "1_1") (pintype "passive"))
      (node (ref "U6") (pin "2") (pinfunction "QC_2") (pintype "tri_state"))
    )
    (net (code "34") (name "/REL27") (class "Default")
      (node (ref "P4") (pin "12") (pinfunction "12_12") (pintype "passive"))
      (node (ref "R41") (pin "1") (pinfunction "1_1") (pintype "passive"))
      (node (ref "U6") (pin "3") (pinfunction "QD_3") (pintype "tri_state"))
    )
    (net (code "35") (name "/REL28") (class "Default")
      (node (ref "P4") (pin "13") (pinfunction "13_13") (pintype "passive"))
      (node (ref "R45") (pin "1") (pinfunction "1_1") (pintype "passive"))
      (node (ref "U6") (pin "4") (pinfunction "QE_4") (pintype "tri_state"))
    )
    (net (code "36") (name "/REL29") (class "Default")
      (node (ref "P4") (pin "14") (pinfunction "14_14") (pintype "passive"))
      (node (ref "R46") (pin "1") (pinfunction "1_1") (pintype "passive"))
      (node (ref "U6") (pin "5") (pinfunction "QF_5") (pintype "tri_state"))
    )
    (net (code "37") (name "/REL30") (class "Default")
      (node (ref "P4") (pin "15") (pinfunction "15_15") (pintype "passive"))
      (node (ref "R47") (pin "1") (pinfunction "1_1") (pintype "passive"))
      (node (ref "U6") (pin "6") (pinfunction "QG_6") (pintype "tri_state"))
    )
    (net (code "38") (name "/REL31") (class "Default")
      (node (ref "P4") (pin "16") (pinfunction "16_16") (pintype "passive"))
      (node (ref "R48") (pin "1") (pinfunction "1_1") (pintype "passive"))
      (node (ref "U6") (pin "7") (pinfunction "QH_7") (pintype "tri_state"))
    )
    (net (code "39") (name "/SELECT_0") (class "Default")
      (node (ref "R31") (pin "2") (pinfunction "2_2") (pintype "passive"))
      (node (ref "U4") (pin "6") (pinfunction "PA0_6") (pintype "bidirectional"))
    )
    (net (code "40") (name "/SELECT_1") (class "Default")
      (node (ref "R32") (pin "2") (pinfunction "2_2") (pintype "passive"))
      (node (ref "U4") (pin "12") (pinfunction "PA6_12") (pintype "bidirectional"))
    )
    (net (code "41") (name "/SELECT_2") (class "Default")
      (node (ref "R34") (pin "2") (pinfunction "2_2") (pintype "passive"))
      (node (ref "U4") (pin "17") (pinfunction "PA9_17") (pintype "bidirectional"))
    )
    (net (code "42") (name "/SELECT_3") (class "Default")
      (node (ref "R37") (pin "2") (pinfunction "2_2") (pintype "passive"))
      (node (ref "U4") (pin "18") (pinfunction "PA10_18") (pintype "bidirectional"))
    )
    (net (code "43") (name "/SELECT_4") (class "Default")
      (node (ref "R38") (pin "2") (pinfunction "2_2") (pintype "passive"))
      (node (ref "U4") (pin "3") (pinfunction "PF1-OSC_OUT(PF1)_3") (pintype "bidirectional"))
    )
    (net (code "44") (name "/SELECT_16_32") (class "Default")
      (node (ref "R29") (pin "2") (pinfunction "2_2") (pintype "passive"))
      (node (ref "U4") (pin "14") (pinfunction "PB1_14") (pintype "bidirectional"))
    )
    (net (code "45") (name "/SPI1_CSN") (class "Default")
      (node (ref "Q4") (pin "2") (pinfunction "S_2") (pintype "passive"))
      (node (ref "R42") (pin "2") (pinfunction "2_2") (pintype "passive"))
      (node (ref "U4") (pin "10") (pinfunction "PA4_10") (pintype "bidirectional"))
    )
    (net (code "46") (name "/SPI1_MOSI") (class "Default")
      (node (ref "Q3") (pin "2") (pinfunction "S_2") (pintype "passive"))
      (node (ref "R35") (pin "2") (pinfunction "2_2") (pintype "passive"))
      (node (ref "U4") (pin "13") (pinfunction "PA7_13") (pintype "bidirectional"))
    )
    (net (code "47") (name "/SPI1_SCK") (class "Default")
      (node (ref "Q2") (pin "2") (pinfunction "S_2") (pintype "passive"))
      (node (ref "R26") (pin "2") (pinfunction "2_2") (pintype "passive"))
      (node (ref "U4") (pin "11") (pinfunction "PA5_11") (pintype "bidirectional"))
    )
    (net (code "48") (name "/SWCLK") (class "Default")
      (node (ref "P3") (pin "1") (pinfunction "1_1") (pintype "passive"))
      (node (ref "R44") (pin "1") (pinfunction "1_1") (pintype "passive"))
      (node (ref "U4") (pin "20") (pinfunction "PA14(SWCLK)_20") (pintype "bidirectional"))
    )
    (net (code "49") (name "/SWDIO") (class "Default")
      (node (ref "P3") (pin "3") (pinfunction "3_3") (pintype "passive"))
      (node (ref "U4") (pin "19") (pinfunction "PA13(SWDIO)_19") (pintype "bidirectional"))
    )
    (net (code "50") (name "/USART1_DE") (class "Default")
      (node (ref "U2") (pin "2") (pinfunction "~{RE}_2") (pintype "input"))
      (node (ref "U2") (pin "3") (pinfunction "DE_3") (pintype "input"))
      (node (ref "U4") (pin "7") (pinfunction "PA1_7") (pintype "bidirectional"))
    )
    (net (code "51") (name "/USART1_RX") (class "Default")
      (node (ref "R7") (pin "1") (pinfunction "1_1") (pintype "passive"))
      (node (ref "U4") (pin "9") (pinfunction "PA3_9") (pintype "bidirectional"))
    )
    (net (code "52") (name "/USART1_TX") (class "Default")
      (node (ref "U2") (pin "4") (pinfunction "D_4") (pintype "input"))
      (node (ref "U4") (pin "8") (pinfunction "PA2_8") (pintype "bidirectional"))
    )
    (net (code "53") (name "Net-(D1-K)") (class "Default")
      (node (ref "D1") (pin "2") (pinfunction "K_2") (pintype "passive"))
      (node (ref "R1") (pin "1") (pinfunction "1_1") (pintype "passive"))
    )
    (net (code "54") (name "Net-(D2-K)") (class "Default")
      (node (ref "D2") (pin "2") (pinfunction "K_2") (pintype "passive"))
      (node (ref "R2") (pin "1") (pinfunction "1_1") (pintype "passive"))
    )
    (net (code "55") (name "Net-(D3-K)") (class "Default")
      (node (ref "D3") (pin "2") (pinfunction "K_2") (pintype "passive"))
      (node (ref "R3") (pin "1") (pinfunction "1_1") (pintype "passive"))
    )
    (net (code "56") (name "Net-(D4-K)") (class "Default")
      (node (ref "D4") (pin "2") (pinfunction "K_2") (pintype "passive"))
      (node (ref "R4") (pin "1") (pinfunction "1_1") (pintype "passive"))
    )
    (net (code "57") (name "Net-(D5-K)") (class "Default")
      (node (ref "D5") (pin "2") (pinfunction "K_2") (pintype "passive"))
      (node (ref "R5") (pin "1") (pinfunction "1_1") (pintype "passive"))
    )
    (net (code "58") (name "Net-(D6-K)") (class "Default")
      (node (ref "D6") (pin "2") (pinfunction "K_2") (pintype "passive"))
      (node (ref "R6") (pin "1") (pinfunction "1_1") (pintype "passive"))
    )
    (net (code "59") (name "Net-(D7-K)") (class "Default")
      (node (ref "D7") (pin "2") (pinfunction "K_2") (pintype "passive"))
      (node (ref "R8") (pin "1") (pinfunction "1_1") (pintype "passive"))
    )
    (net (code "60") (name "Net-(D8-K)") (class "Default")
      (node (ref "D8") (pin "2") (pinfunction "K_2") (pintype "passive"))
      (node (ref "R9") (pin "1") (pinfunction "1_1") (pintype "passive"))
    )
    (net (code "61") (name "Net-(D9-K)") (class "Default")
      (node (ref "D9") (pin "2") (pinfunction "K_2") (pintype "passive"))
      (node (ref "R10") (pin "1") (pinfunction "1_1") (pintype "passive"))
    )
    (net (code "62") (name "Net-(D10-K)") (class "Default")
      (node (ref "D10") (pin "2") (pinfunction "K_2") (pintype "passive"))
      (node (ref "R11") (pin "1") (pinfunction "1_1") (pintype "passive"))
    )
    (net (code "63") (name "Net-(D11-K)") (class "Default")
      (node (ref "D11") (pin "2") (pinfunction "K_2") (pintype "passive"))
      (node (ref "R12") (pin "1") (pinfunction "1_1") (pintype "passive"))
    )
    (net (code "64") (name "Net-(D12-K)") (class "Default")
      (node (ref "D12") (pin "2") (pinfunction "K_2") (pintype "passive"))
      (node (ref "R13") (pin "1") (pinfunction "1_1") (pintype "passive"))
    )
    (net (code "65") (name "Net-(D13-K)") (class "Default")
      (node (ref "D13") (pin "2") (pinfunction "K_2") (pintype "passive"))
      (node (ref "R14") (pin "1") (pinfunction "1_1") (pintype "passive"))
    )
    (net (code "66") (name "Net-(D14-K)") (class "Default")
      (node (ref "D14") (pin "2") (pinfunction "K_2") (pintype "passive"))
      (node (ref "R15") (pin "1") (pinfunction "1_1") (pintype "passive"))
    )
    (net (code "67") (name "Net-(D15-K)") (class "Default")
      (node (ref "D15") (pin "2") (pinfunction "K_2") (pintype "passive"))
      (node (ref "R16") (pin "1") (pinfunction "1_1") (pintype "passive"))
    )
    (net (code "68") (name "Net-(D16-K)") (class "Default")
      (node (ref "D16") (pin "2") (pinfunction "K_2") (pintype "passive"))
      (node (ref "R18") (pin "1") (pinfunction "1_1") (pintype "passive"))
    )
    (net (code "69") (name "Net-(D17-A)") (class "Default")
      (node (ref "D17") (pin "1") (pinfunction "A_1") (pintype "passive"))
      (node (ref "R20") (pin "2") (pinfunction "2_2") (pintype "passive"))
    )
    (net (code "70") (name "Net-(D18-A)") (class "Default")
      (node (ref "D18") (pin "1") (pinfunction "A_1") (pintype "passive"))
      (node (ref "R21") (pin "2") (pinfunction "2_2") (pintype "passive"))
    )
    (net (code "71") (name "Net-(D19-A)") (class "Default")
      (node (ref "D19") (pin "1") (pinfunction "A_1") (pintype "passive"))
      (node (ref "R22") (pin "2") (pinfunction "2_2") (pintype "passive"))
    )
    (net (code "72") (name "Net-(D20-A)") (class "Default")
      (node (ref "D20") (pin "1") (pinfunction "A_1") (pintype "passive"))
      (node (ref "R23") (pin "2") (pinfunction "2_2") (pintype "passive"))
    )
    (net (code "73") (name "Net-(D21-A)") (class "Default")
      (node (ref "D21") (pin "1") (pinfunction "A_1") (pintype "passive"))
      (node (ref "R24") (pin "2") (pinfunction "2_2") (pintype "passive"))
    )
    (net (code "74") (name "Net-(D22-A)") (class "Default")
      (node (ref "D22") (pin "1") (pinfunction "A_1") (pintype "passive"))
      (node (ref "R25") (pin "2") (pinfunction "2_2") (pintype "passive"))
    )
    (net (code "75") (name "Net-(D23-A)") (class "Default")
      (node (ref "D23") (pin "1") (pinfunction "A_1") (pintype "passive"))
      (node (ref "R28") (pin "2") (pinfunction "2_2") (pintype "passive"))
    )
    (net (code "76") (name "Net-(D24-A)") (class "Default")
      (node (ref "D24") (pin "1") (pinfunction "A_1") (pintype "passive"))
      (node (ref "R30") (pin "2") (pinfunction "2_2") (pintype "passive"))
    )
    (net (code "77") (name "Net-(D25-A)") (class "Default")
      (node (ref "D25") (pin "1") (pinfunction "A_1") (pintype "passive"))
      (node (ref "R33") (pin "2") (pinfunction "2_2") (pintype "passive"))
    )
    (net (code "78") (name "Net-(D26-A)") (class "Default")
      (node (ref "D26") (pin "1") (pinfunction "A_1") (pintype "passive"))
      (node (ref "R39") (pin "2") (pinfunction "2_2") (pintype "passive"))
    )
    (net (code "79") (name "Net-(D27-A)") (class "Default")
      (node (ref "D27") (pin "1") (pinfunction "A_1") (pintype "passive"))
      (node (ref "R40") (pin "2") (pinfunction "2_2") (pintype "passive"))
    )
    (net (code "80") (name "Net-(D28-A)") (class "Default")
      (node (ref "D28") (pin "1") (pinfunction "A_1") (pintype "passive"))
      (node (ref "R41") (pin "2") (pinfunction "2_2") (pintype "passive"))
    )
    (net (code "81") (name "Net-(D29-A)") (class "Default")
      (node (ref "D29") (pin "1") (pinfunction "A_1") (pintype "passive"))
      (node (ref "R44") (pin "2") (pinfunction "2_2") (pintype "passive"))
    )
    (net (code "82") (name "Net-(D30-A)") (class "Default")
      (node (ref "D30") (pin "1") (pinfunction "A_1") (pintype "passive"))
      (node (ref "R45") (pin "2") (pinfunction "2_2") (pintype "passive"))
    )
    (net (code "83") (name "Net-(D31-A)") (class "Default")
      (node (ref "D31") (pin "1") (pinfunction "A_1") (pintype "passive"))
      (node (ref "R46") (pin "2") (pinfunction "2_2") (pintype "passive"))
    )
    (net (code "84") (name "Net-(D32-A)") (class "Default")
      (node (ref "D32") (pin "1") (pinfunction "A_1") (pintype "passive"))
      (node (ref "R47") (pin "2") (pinfunction "2_2") (pintype "passive"))
    )
    (net (code "85") (name "Net-(D33-A)") (class "Default")
      (node (ref "D33") (pin "1") (pinfunction "A_1") (pintype "passive"))
      (node (ref "R48") (pin "2") (pinfunction "2_2") (pintype "passive"))
    )
    (net (code "86") (name "Net-(Q1-B)") (class "Default")
      (node (ref "Q1") (pin "1") (pinfunction "B_1") (pintype "passive"))
      (node (ref "R19") (pin "2") (pinfunction "2_2") (pintype "passive"))
    )
    (net (code "87") (name "Net-(U1-QH')") (class "Default")
      (node (ref "U1") (pin "9") (pinfunction "QH'_9") (pintype "output"))
      (node (ref "U3") (pin "14") (pinfunction "SER_14") (pintype "input"))
    )
    (net (code "88") (name "Net-(U2-A)") (class "Default")
      (node (ref "P1") (pin "2") (pinfunction "2_2") (pintype "passive"))
      (node (ref "U2") (pin "6") (pinfunction "A_6") (pintype "bidirectional"))
    )
    (net (code "89") (name "Net-(U2-R)") (class "Default")
      (node (ref "R7") (pin "2") (pinfunction "2_2") (pintype "passive"))
      (node (ref "U2") (pin "1") (pinfunction "R_1") (pintype "tri_state"))
    )
    (net (code "90") (name "Net-(U2-~{B})") (class "Default")
      (node (ref "P1") (pin "1") (pinfunction "1_1") (pintype "passive"))
      (node (ref "U2") (pin "7") (pinfunction "~{B}_7") (pintype "bidirectional"))
    )
    (net (code "91") (name "Net-(U3-QH')") (class "Default")
      (node (ref "U3") (pin "9") (pinfunction "QH'_9") (pintype "output"))
      (node (ref "U5") (pin "14") (pinfunction "SER_14") (pintype "input"))
    )
    (net (code "92") (name "Net-(U4-NRST)") (class "Default")
      (node (ref "C4") (pin "1") (pinfunction "1_1") (pintype "passive"))
      (node (ref "U4") (pin "4") (pinfunction "NRST_4") (pintype "bidirectional"))
    )
    (net (code "93") (name "Net-(U4-PF0-OSC_IN(PF0))") (class "Default")
      (node (ref "R19") (pin "1") (pinfunction "1_1") (pintype "passive"))
      (node (ref "U4") (pin "2") (pinfunction "PF0-OSC_IN(PF0)_2") (pintype "bidirectional"))
    )
    (net (code "94") (name "Net-(U5-QH')") (class "Default")
      (node (ref "U5") (pin "9") (pinfunction "QH'_9") (pintype "output"))
      (node (ref "U6") (pin "14") (pinfunction "SER_14") (pintype "input"))
    )
    (net (code "95") (name "Net-(U7-IN)") (class "Default")
      (node (ref "C15") (pin "2") (pinfunction "2_2") (pintype "passive"))
      (node (ref "C19") (pin "1") (pinfunction "1_1") (pintype "passive"))
      (node (ref "P5") (pin "1") (pinfunction "1_1") (pintype "passive"))
      (node (ref "U7") (pin "1") (pinfunction "IN_1") (pintype "power_in"))
    )
    (net (code "96") (name "VSS") (class "Default")
      (node (ref "C1") (pin "2") (pinfunction "2_2") (pintype "passive"))
      (node (ref "C10") (pin "2") (pinfunction "2_2") (pintype "passive"))
      (node (ref "C11") (pin "1") (pinfunction "1_1") (pintype "passive"))
      (node (ref "C12") (pin "1") (pinfunction "1_1") (pintype "passive"))
      (node (ref "C13") (pin "1") (pinfunction "1_1") (pintype "passive"))
      (node (ref "C14") (pin "2") (pinfunction "2_2") (pintype "passive"))
      (node (ref "C15") (pin "1") (pinfunction "1_1") (pintype "passive"))
      (node (ref "C16") (pin "1") (pinfunction "1_1") (pintype "passive"))
      (node (ref "C17") (pin "1") (pinfunction "1_1") (pintype "passive"))
      (node (ref "C18") (pin "1") (pinfunction "1_1") (pintype "passive"))
      (node (ref "C19") (pin "2") (pinfunction "2_2") (pintype "passive"))
      (node (ref "C2") (pin "2") (pinfunction "2_2") (pintype "passive"))
      (node (ref "C3") (pin "2") (pinfunction "2_2") (pintype "passive"))
      (node (ref "C4") (pin "2") (pinfunction "2_2") (pintype "passive"))
      (node (ref "C5") (pin "2") (pinfunction "2_2") (pintype "passive"))
      (node (ref "C6") (pin "2") (pinfunction "2_2") (pintype "passive"))
      (node (ref "C7") (pin "2") (pinfunction "2_2") (pintype "passive"))
      (node (ref "C8") (pin "2") (pinfunction "2_2") (pintype "passive"))
      (node (ref "C9") (pin "2") (pinfunction "2_2") (pintype "passive"))
      (node (ref "D17") (pin "2") (pinfunction "K_2") (pintype "passive"))
      (node (ref "D18") (pin "2") (pinfunction "K_2") (pintype "passive"))
      (node (ref "D19") (pin "2") (pinfunction "K_2") (pintype "passive"))
      (node (ref "D20") (pin "2") (pinfunction "K_2") (pintype "passive"))
      (node (ref "D21") (pin "2") (pinfunction "K_2") (pintype "passive"))
      (node (ref "D22") (pin "2") (pinfunction "K_2") (pintype "passive"))
      (node (ref "D23") (pin "2") (pinfunction "K_2") (pintype "passive"))
      (node (ref "D24") (pin "2") (pinfunction "K_2") (pintype "passive"))
      (node (ref "D25") (pin "2") (pinfunction "K_2") (pintype "passive"))
      (node (ref "D26") (pin "2") (pinfunction "K_2") (pintype "passive"))
      (node (ref "D27") (pin "2") (pinfunction "K_2") (pintype "passive"))
      (node (ref "D28") (pin "2") (pinfunction "K_2") (pintype "passive"))
      (node (ref "D29") (pin "2") (pinfunction "K_2") (pintype "passive"))
      (node (ref "D30") (pin "2") (pinfunction "K_2") (pintype "passive"))
      (node (ref "D31") (pin "2") (pinfunction "K_2") (pintype "passive"))
      (node (ref "D32") (pin "2") (pinfunction "K_2") (pintype "passive"))
      (node (ref "D33") (pin "2") (pinfunction "K_2") (pintype "passive"))
      (node (ref "P2") (pin "19") (pinfunction "19_19") (pintype "passive"))
      (node (ref "P2") (pin "20") (pinfunction "20_20") (pintype "passive"))
      (node (ref "P3") (pin "2") (pinfunction "2_2") (pintype "passive"))
      (node (ref "P4") (pin "17") (pinfunction "17_17") (pintype "passive"))
      (node (ref "P5") (pin "2") (pinfunction "2_2") (pintype "passive"))
      (node (ref "Q1") (pin "2") (pinfunction "E_2") (pintype "passive"))
      (node (ref "R29") (pin "1") (pinfunction "1_1") (pintype "passive"))
      (node (ref "R31") (pin "1") (pinfunction "1_1") (pintype "passive"))
      (node (ref "R32") (pin "1") (pinfunction "1_1") (pintype "passive"))
      (node (ref "R34") (pin "1") (pinfunction "1_1") (pintype "passive"))
      (node (ref "R37") (pin "1") (pinfunction "1_1") (pintype "passive"))
      (node (ref "R38") (pin "1") (pinfunction "1_1") (pintype "passive"))
      (node (ref "U1") (pin "8") (pinfunction "GND_8") (pintype "power_in"))
      (node (ref "U2") (pin "5") (pinfunction "GND_5") (pintype "power_in"))
      (node (ref "U3") (pin "8") (pinfunction "GND_8") (pintype "power_in"))
      (node (ref "U4") (pin "1") (pinfunction "BOOT0_1") (pintype "input"))
      (node (ref "U4") (pin "15") (pinfunction "VSS_15") (pintype "power_in"))
      (node (ref "U5") (pin "8") (pinfunction "GND_8") (pintype "power_in"))
      (node (ref "U6") (pin "8") (pinfunction "GND_8") (pintype "power_in"))
      (node (ref "U7") (pin "4") (pinfunction "GND_4") (pintype "power_in"))
      (node (ref "U8") (pin "1") (pinfunction "GND_1") (pintype "power_in"))
    )
    (net (code "97") (name "unconnected-(U6-QH'-Pad9)") (class "Default")
      (node (ref "U6") (pin "9") (pinfunction "QH'_9") (pintype "output"))
    )
  )
)
